# PDM.net
KiCad netlist of a schematic drawn in Altium Designer
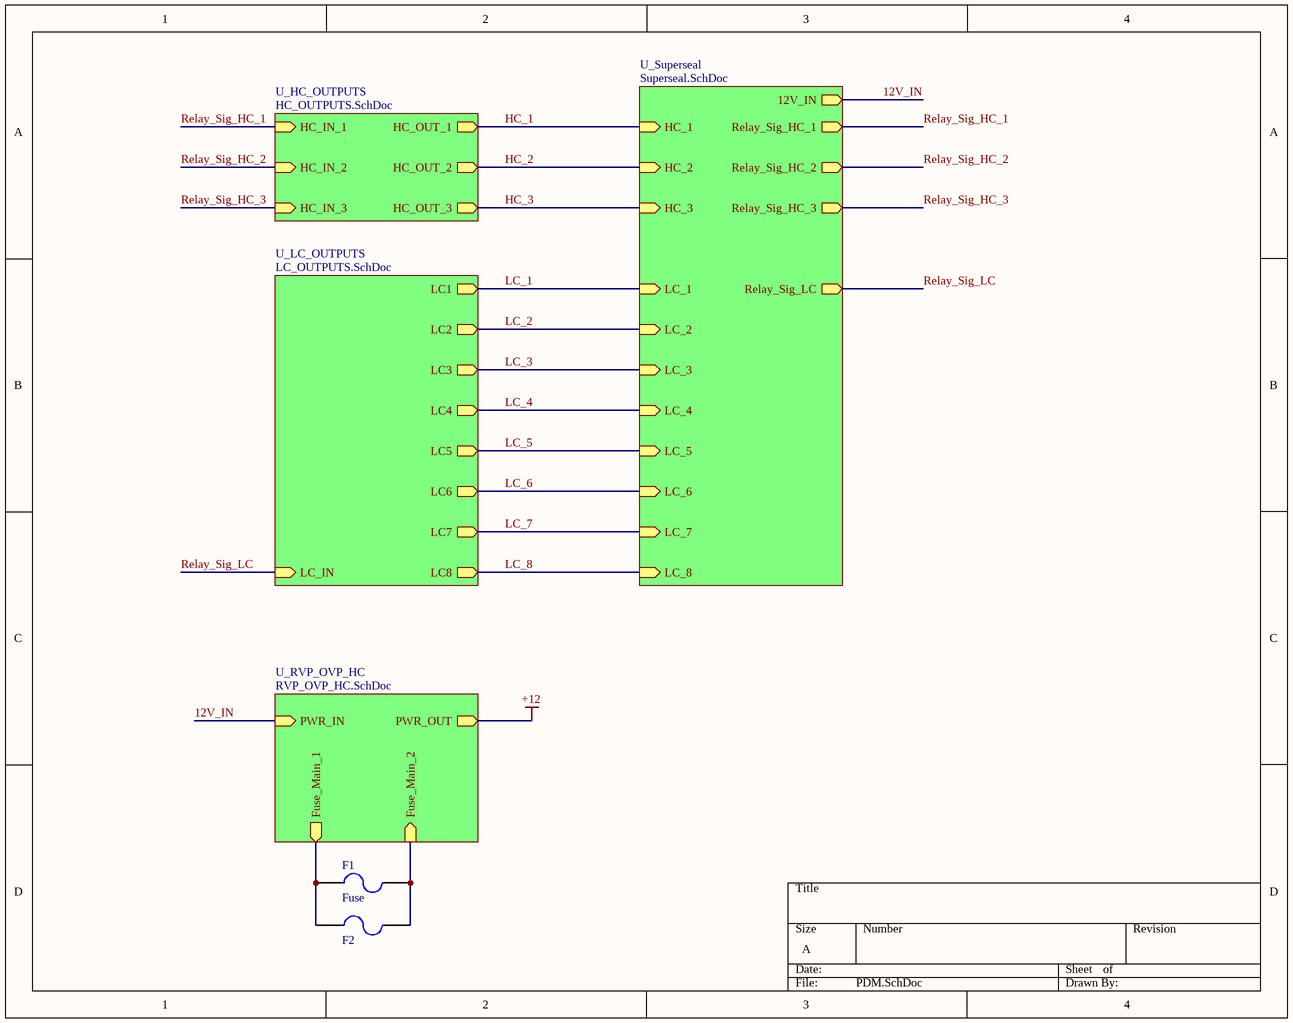
[diagram p0: PDM.SchDoc]

(export (version "E")
  (design (tool "Eeschema 10.0.6"))
  (components
    (comp (ref "F1")
      (value "Fuse")
      (footprint "3568-MiniFuseHolder")
      (libsource (lib "Altium-Lib") (part "Fuse"))
    )
    (comp (ref "F2")
      (value "Fuse")
      (footprint "3568-MiniFuseHolder")
      (libsource (lib "Altium-Lib") (part "Fuse"))
    )
  )
  (nets
    (net (code "3") (name "/Fuse_Main_1") (class "Default")
      (node (ref "F1") (pin "1") (pinfunction "1_1") (pintype "passive"))
      (node (ref "F2") (pin "1") (pinfunction "1_1") (pintype "passive"))
    )
    (net (code "4") (name "/Fuse_Main_2") (class "Default")
      (node (ref "F1") (pin "2") (pinfunction "2_2") (pintype "passive"))
      (node (ref "F2") (pin "2") (pinfunction "2_2") (pintype "passive"))
    )
  )
)
